# shudian.net
KiCad netlist of a schematic drawn in Altium Designer
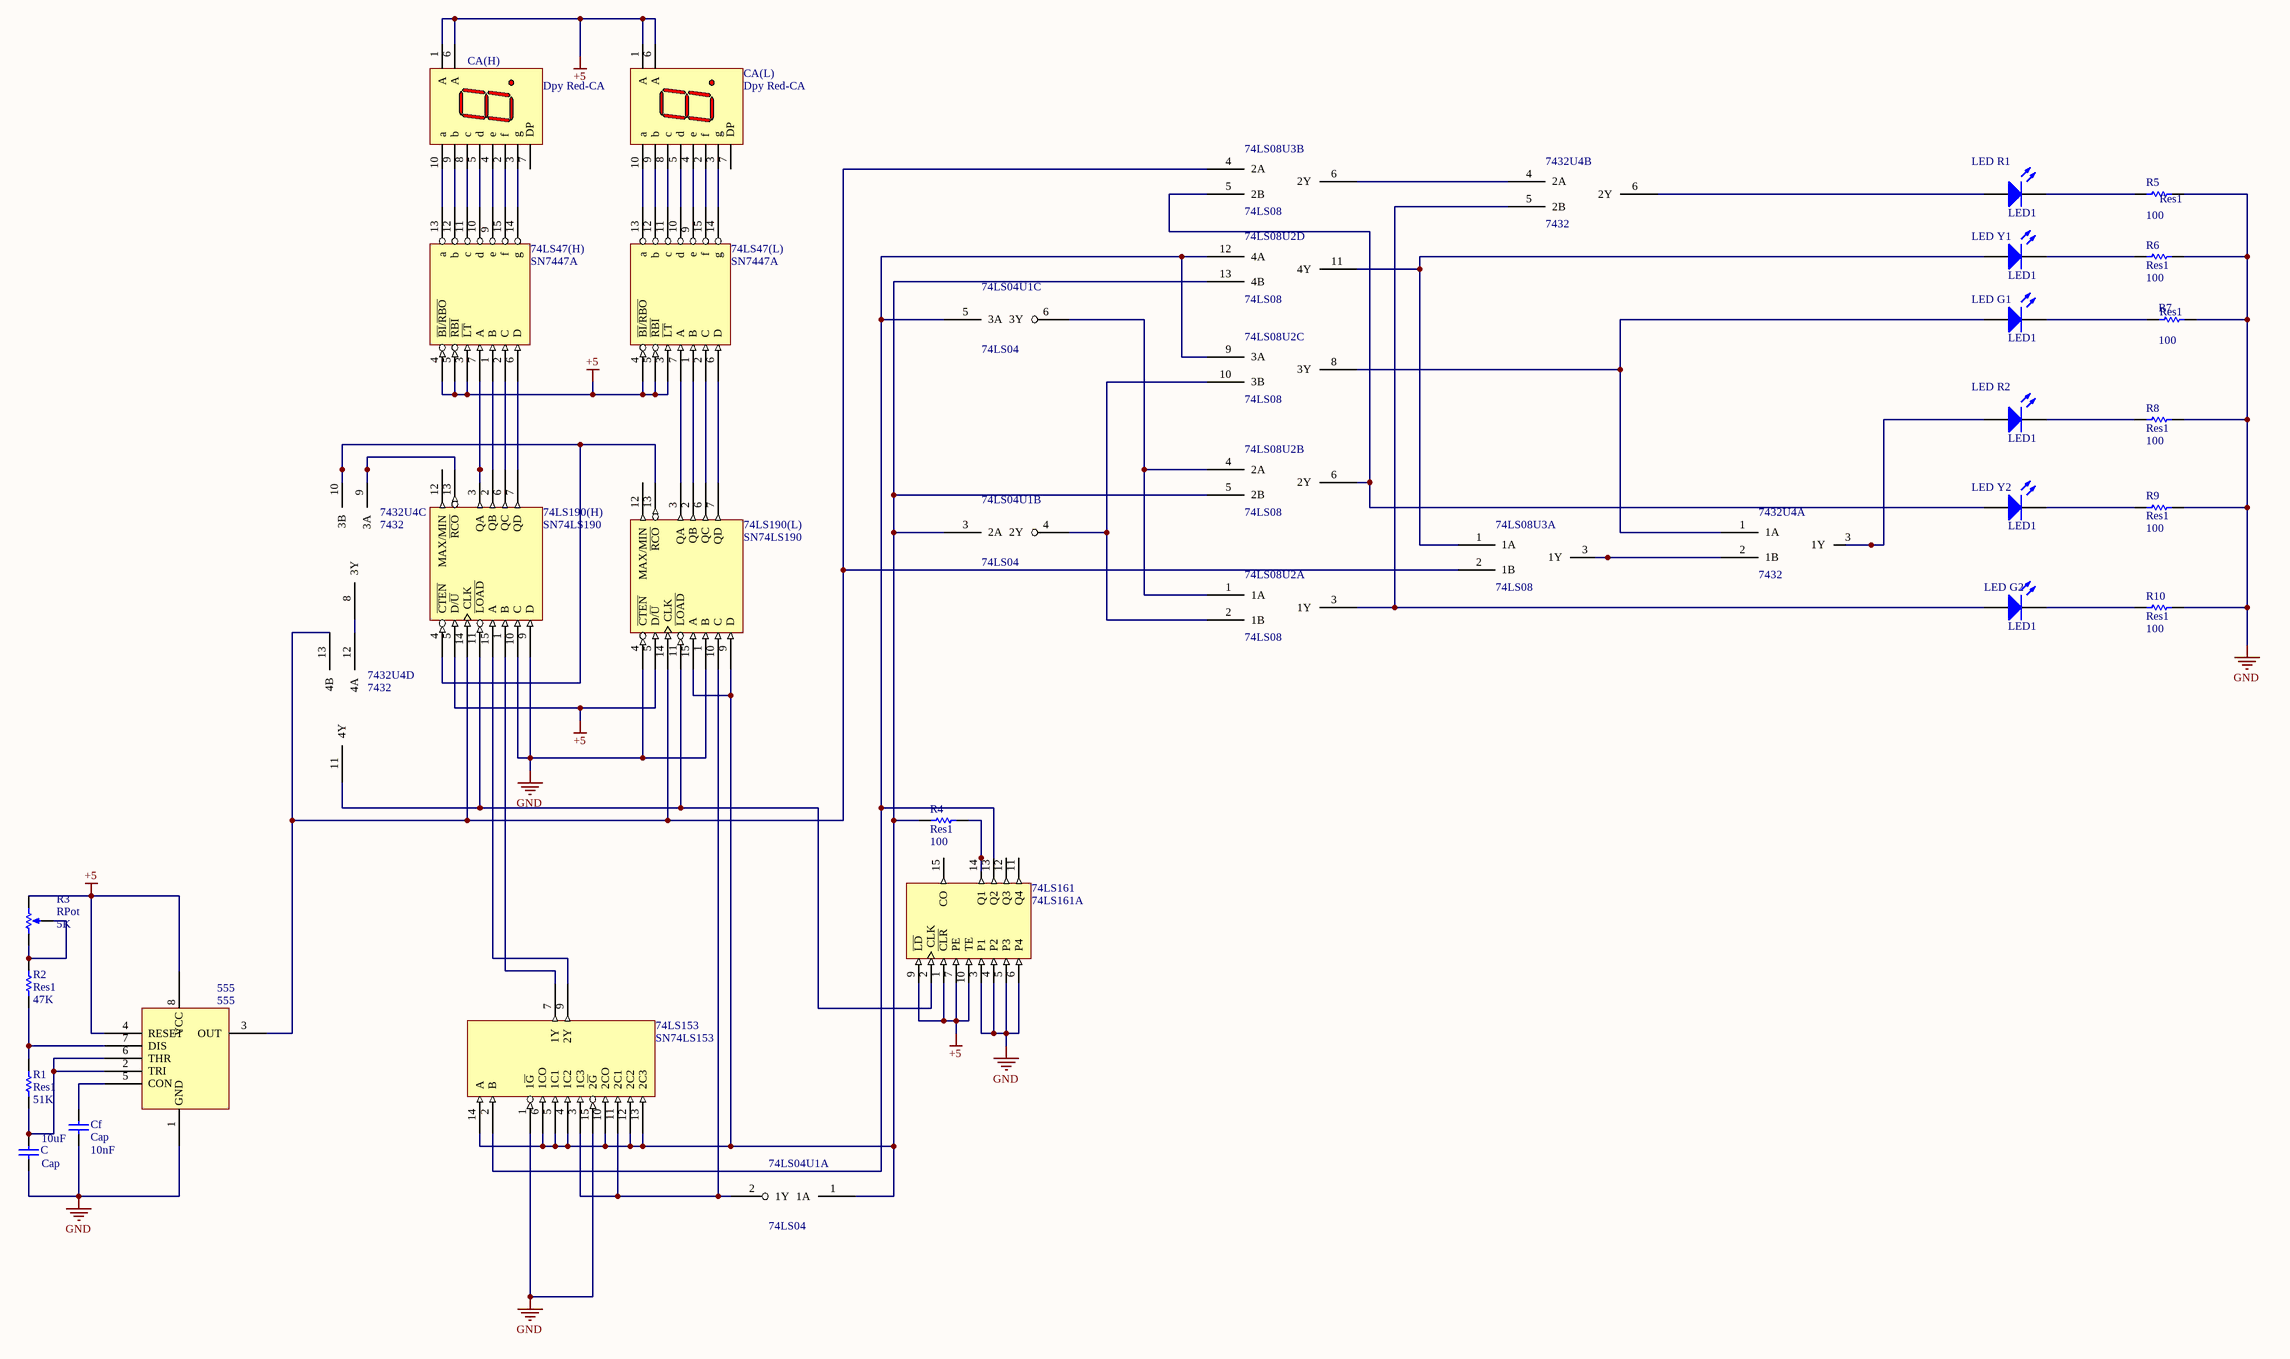
[diagram p0: shudian.schdoc]

(export (version "E")
  (design (tool "Eeschema 10.0.6"))
  (components
    (comp (ref "74LS04U1") (value "74LS04") (footprint "DIP14") (libsource (lib "shudian") (part "74LS04")))
    (comp (ref "74LS08U2") (value "74LS08") (footprint "DIP14") (libsource (lib "shudian") (part "74LS08")))
    (comp (ref "74LS08U3") (value "74LS08") (footprint "DIP14") (libsource (lib "shudian") (part "74LS08")))
    (comp (ref "74LS47(H)")
      (value "SN7447A")
      (footprint "DIP16")
      (description "BCD-To-SEVEN-SEGMENT DEC DRV")
      (libsource (lib "1.4 - 74系列TTL芯片") (part "SN7446A"))
    )
    (comp (ref "74LS47(L)")
      (value "SN7447A")
      (footprint "DIP-16")
      (description "BCD-To-SEVEN-SEGMENT DEC DRV")
      (libsource (lib "1.4 - 74系列TTL芯片") (part "SN7446A"))
    )
    (comp (ref "74LS153")
      (value "SN74LS153")
      (footprint "DIP16")
      (description "DUAL 4-1 LINE DATA SELEC/MUX")
      (libsource (lib "1.4 - 74系列TTL芯片") (part "SN74LS153"))
    )
    (comp (ref "74LS161")
      (value "74LS161A")
      (footprint "DIP-16")
      (description "Synchronous 4-Bit Binary Counter with Direct Clear")
      (libsource (lib "1.4 - 74系列TTL芯片") (part "74LS161A"))
    )
    (comp (ref "74LS190(H)")
      (value "SN74LS190")
      (footprint "DIP-16")
      (description "SYN UP/DOWN CNT DOWN/UP MODE CONTTOL")
      (libsource (lib "1.4 - 74系列TTL芯片") (part "SN74LS190"))
    )
    (comp (ref "74LS190(L)")
      (value "SN74LS190")
      (footprint "DIP-16")
      (description "SYN UP/DOWN CNT DOWN/UP MODE CONTTOL")
      (libsource (lib "1.4 - 74系列TTL芯片") (part "SN74LS190"))
    )
    (comp (ref "555") (value "555") (footprint "DIP8") (libsource (lib "Schlib1") (part "555")))
    (comp (ref "7432U4") (value "7432") (footprint "DIP14") (libsource (lib "shudian") (part "7432")))
    (comp (ref "C")
      (value "Cap")
      (footprint "RAD-0.3")
      (description "Capacitor")
      (fields (field (name "ALTIUM_VALUE") "10uF") (field (name "PUBLISHER") "Altium Limited"))
      (libsource (lib "Miscellaneous Devices") (part "Cap"))
    )
    (comp (ref "CA(H)")
      (value "Dpy Red-CA")
      (footprint "A")
      (description "7.62 mm Black Surface HER 7-Segment Display: CA, RH DP")
      (fields (field (name "PUBLISHER") "Altium Limited"))
      (libsource (lib "Miscellaneous Devices") (part "Dpy Red-CA"))
    )
    (comp (ref "CA(L)")
      (value "Dpy Red-CA")
      (footprint "A")
      (description "7.62 mm Black Surface HER 7-Segment Display: CA, RH DP")
      (fields (field (name "PUBLISHER") "Altium Limited"))
      (libsource (lib "Miscellaneous Devices") (part "Dpy Red-CA"))
    )
    (comp (ref "Cf")
      (value "Cap")
      (footprint "RAD-0.3")
      (description "Capacitor")
      (fields (field (name "ALTIUM_VALUE") "10nF") (field (name "PUBLISHER") "Altium Limited"))
      (libsource (lib "Miscellaneous Devices") (part "Cap"))
    )
    (comp (ref "LED G1")
      (value "LED1")
      (footprint "LED-1")
      (description "Typical RED GaAs LED")
      (fields (field (name "PUBLISHER") "Altium Limited"))
      (libsource (lib "Miscellaneous Devices") (part "LED1"))
    )
    (comp (ref "LED G2")
      (value "LED1")
      (footprint "LED-1")
      (description "Typical RED GaAs LED")
      (fields (field (name "PUBLISHER") "Altium Limited"))
      (libsource (lib "Miscellaneous Devices") (part "LED1"))
    )
    (comp (ref "LED R1")
      (value "LED1")
      (footprint "LED-1")
      (description "Typical RED GaAs LED")
      (fields (field (name "PUBLISHER") "Altium Limited"))
      (libsource (lib "Miscellaneous Devices") (part "LED1"))
    )
    (comp (ref "LED R2")
      (value "LED1")
      (footprint "LED-1")
      (description "Typical RED GaAs LED")
      (fields (field (name "PUBLISHER") "Altium Limited"))
      (libsource (lib "Miscellaneous Devices") (part "LED1"))
    )
    (comp (ref "LED Y1")
      (value "LED1")
      (footprint "LED-1")
      (description "Typical RED GaAs LED")
      (fields (field (name "PUBLISHER") "Altium Limited"))
      (libsource (lib "Miscellaneous Devices") (part "LED1"))
    )
    (comp (ref "LED Y2")
      (value "LED1")
      (footprint "LED-1")
      (description "Typical RED GaAs LED")
      (fields (field (name "PUBLISHER") "Altium Limited"))
      (libsource (lib "Miscellaneous Devices") (part "LED1"))
    )
    (comp (ref "R1")
      (value "Res1")
      (footprint "AXIAL-0.3")
      (description "Resistor")
      (fields (field (name "ALTIUM_VALUE") "51K") (field (name "PUBLISHER") "Altium Limited"))
      (libsource (lib "Miscellaneous Devices") (part "Res1"))
    )
    (comp (ref "R2")
      (value "Res1")
      (footprint "AXIAL-0.3")
      (description "Resistor")
      (fields (field (name "ALTIUM_VALUE") "47K") (field (name "PUBLISHER") "Altium Limited"))
      (libsource (lib "Miscellaneous Devices") (part "Res1"))
    )
    (comp (ref "R3")
      (value "RPot")
      (footprint "VR5")
      (description "Potentiometer")
      (fields (field (name "ALTIUM_VALUE") "5K") (field (name "PUBLISHER") "Altium Limited"))
      (libsource (lib "Miscellaneous Devices") (part "RPot"))
    )
    (comp (ref "R4")
      (value "Res1")
      (footprint "AXIAL-0.3")
      (description "Resistor")
      (fields (field (name "ALTIUM_VALUE") "100") (field (name "PUBLISHER") "Altium Limited"))
      (libsource (lib "Miscellaneous Devices") (part "Res1"))
    )
    (comp (ref "R5")
      (value "Res1")
      (footprint "AXIAL-0.3")
      (description "Resistor")
      (fields (field (name "ALTIUM_VALUE") "100") (field (name "PUBLISHER") "Altium Limited"))
      (libsource (lib "Miscellaneous Devices") (part "Res1"))
    )
    (comp (ref "R6")
      (value "Res1")
      (footprint "AXIAL-0.3")
      (description "Resistor")
      (fields (field (name "ALTIUM_VALUE") "100") (field (name "PUBLISHER") "Altium Limited"))
      (libsource (lib "Miscellaneous Devices") (part "Res1"))
    )
    (comp (ref "R7")
      (value "Res1")
      (footprint "AXIAL-0.3")
      (description "Resistor")
      (fields (field (name "ALTIUM_VALUE") "100") (field (name "PUBLISHER") "Altium Limited"))
      (libsource (lib "Miscellaneous Devices") (part "Res1"))
    )
    (comp (ref "R8")
      (value "Res1")
      (footprint "AXIAL-0.3")
      (description "Resistor")
      (fields (field (name "ALTIUM_VALUE") "100") (field (name "PUBLISHER") "Altium Limited"))
      (libsource (lib "Miscellaneous Devices") (part "Res1"))
    )
    (comp (ref "R9")
      (value "Res1")
      (footprint "AXIAL-0.3")
      (description "Resistor")
      (fields (field (name "ALTIUM_VALUE") "100") (field (name "PUBLISHER") "Altium Limited"))
      (libsource (lib "Miscellaneous Devices") (part "Res1"))
    )
    (comp (ref "R10")
      (value "Res1")
      (footprint "AXIAL-0.3")
      (description "Resistor")
      (fields (field (name "ALTIUM_VALUE") "100") (field (name "PUBLISHER") "Altium Limited"))
      (libsource (lib "Miscellaneous Devices") (part "Res1"))
    )
  )
  (nets
    (net (code "1") (name "+5") (class "Default")
      (node (ref "555") (pin "4") (pinfunction "RESET_4") (pintype "passive"))
      (node (ref "555") (pin "8") (pinfunction "VCC_8") (pintype "passive"))
      (node (ref "74LS161") (pin "1") (pinfunction "~{CLR}_1") (pintype "input"))
      (node (ref "74LS161") (pin "10") (pinfunction "TE_10") (pintype "input"))
      (node (ref "74LS161") (pin "7") (pinfunction "PE_7") (pintype "input"))
      (node (ref "74LS161") (pin "9") (pinfunction "~{LD}_9") (pintype "input"))
      (node (ref "74LS190(H)") (pin "5") (pinfunction "D/~{U}_5") (pintype "input"))
      (node (ref "74LS190(L)") (pin "5") (pinfunction "D/~{U}_5") (pintype "input"))
      (node (ref "74LS47(H)") (pin "3") (pinfunction "~{LT}_3") (pintype "input"))
      (node (ref "74LS47(H)") (pin "4") (pinfunction "~{BI}/~{RBO}_4") (pintype "input"))
      (node (ref "74LS47(H)") (pin "5") (pinfunction "~{RBI}_5") (pintype "input"))
      (node (ref "74LS47(L)") (pin "3") (pinfunction "~{LT}_3") (pintype "input"))
      (node (ref "74LS47(L)") (pin "4") (pinfunction "~{BI}/~{RBO}_4") (pintype "input"))
      (node (ref "74LS47(L)") (pin "5") (pinfunction "~{RBI}_5") (pintype "input"))
      (node (ref "CA(H)") (pin "1") (pinfunction "A_1") (pintype "passive"))
      (node (ref "CA(H)") (pin "6") (pinfunction "A_6") (pintype "passive"))
      (node (ref "CA(L)") (pin "1") (pinfunction "A_1") (pintype "passive"))
      (node (ref "CA(L)") (pin "6") (pinfunction "A_6") (pintype "passive"))
      (node (ref "R3") (pin "2") (pinfunction "BOT_2") (pintype "passive"))
    )
    (net (code "2") (name "GND") (class "Default")
      (node (ref "555") (pin "1") (pinfunction "GND_1") (pintype "passive"))
      (node (ref "74LS153") (pin "1") (pinfunction "1~{G}_1") (pintype "input"))
      (node (ref "74LS153") (pin "15") (pinfunction "2~{G}_15") (pintype "input"))
      (node (ref "74LS153") (pin "8") (pinfunction "GND_8") (pintype "power_in"))
      (node (ref "74LS161") (pin "3") (pinfunction "P1_3") (pintype "input"))
      (node (ref "74LS161") (pin "4") (pinfunction "P2_4") (pintype "input"))
      (node (ref "74LS161") (pin "5") (pinfunction "P3_5") (pintype "input"))
      (node (ref "74LS161") (pin "6") (pinfunction "P4_6") (pintype "input"))
      (node (ref "74LS161") (pin "8") (pinfunction "GND_8") (pintype "power_in"))
      (node (ref "74LS190(H)") (pin "10") (pinfunction "C_10") (pintype "input"))
      (node (ref "74LS190(H)") (pin "8") (pinfunction "GND_8") (pintype "power_in"))
      (node (ref "74LS190(H)") (pin "9") (pinfunction "D_9") (pintype "input"))
      (node (ref "74LS190(L)") (pin "1") (pinfunction "B_1") (pintype "input"))
      (node (ref "74LS190(L)") (pin "4") (pinfunction "~{CTEN}_4") (pintype "input"))
      (node (ref "74LS190(L)") (pin "8") (pinfunction "GND_8") (pintype "power_in"))
      (node (ref "74LS47(H)") (pin "8") (pinfunction "GND_8") (pintype "power_in"))
      (node (ref "74LS47(L)") (pin "8") (pinfunction "GND_8") (pintype "power_in"))
      (node (ref "C") (pin "1") (pinfunction "1_1") (pintype "passive"))
      (node (ref "Cf") (pin "1") (pinfunction "1_1") (pintype "passive"))
      (node (ref "R10") (pin "2") (pinfunction "2_2") (pintype "passive"))
      (node (ref "R5") (pin "2") (pinfunction "2_2") (pintype "passive"))
      (node (ref "R6") (pin "2") (pinfunction "2_2") (pintype "passive"))
      (node (ref "R7") (pin "2") (pinfunction "2_2") (pintype "passive"))
      (node (ref "R8") (pin "2") (pinfunction "2_2") (pintype "passive"))
      (node (ref "R9") (pin "2") (pinfunction "2_2") (pintype "passive"))
    )
    (net (code "3") (name "Net-(74LS04U1A-1A)") (class "Default")
      (node (ref "74LS04U1") (pin "1") (pinfunction "1A_1") (pintype "passive"))
      (node (ref "74LS04U1") (pin "3") (pinfunction "2A_3") (pintype "passive"))
      (node (ref "74LS08U2") (pin "13") (pinfunction "4B_13") (pintype "passive"))
      (node (ref "74LS08U2") (pin "5") (pinfunction "2B_5") (pintype "passive"))
      (node (ref "74LS153") (pin "10") (pinfunction "2CO_10") (pintype "input"))
      (node (ref "74LS153") (pin "12") (pinfunction "2C2_12") (pintype "input"))
      (node (ref "74LS153") (pin "13") (pinfunction "2C3_13") (pintype "input"))
      (node (ref "74LS153") (pin "14") (pinfunction "A_14") (pintype "input"))
      (node (ref "74LS153") (pin "4") (pinfunction "1C2_4") (pintype "input"))
      (node (ref "74LS153") (pin "5") (pinfunction "1C1_5") (pintype "input"))
      (node (ref "74LS153") (pin "6") (pinfunction "1CO_6") (pintype "input"))
      (node (ref "74LS190(L)") (pin "15") (pinfunction "A_15") (pintype "input"))
      (node (ref "74LS190(L)") (pin "9") (pinfunction "D_9") (pintype "input"))
      (node (ref "R4") (pin "1") (pinfunction "1_1") (pintype "passive"))
    )
    (net (code "4") (name "Net-(74LS04U1A-1Y)") (class "Default")
      (node (ref "74LS04U1") (pin "2") (pinfunction "1Y_2") (pintype "passive"))
      (node (ref "74LS153") (pin "11") (pinfunction "2C1_11") (pintype "input"))
      (node (ref "74LS153") (pin "3") (pinfunction "1C3_3") (pintype "input"))
      (node (ref "74LS190(L)") (pin "10") (pinfunction "C_10") (pintype "input"))
    )
    (net (code "5") (name "Net-(74LS04U1B-2Y)") (class "Default")
      (node (ref "74LS04U1") (pin "4") (pinfunction "2Y_4") (pintype "passive"))
      (node (ref "74LS08U2") (pin "10") (pinfunction "3B_10") (pintype "passive"))
      (node (ref "74LS08U2") (pin "2") (pinfunction "1B_2") (pintype "passive"))
    )
    (net (code "6") (name "Net-(74LS04U1C-3A)") (class "Default")
      (node (ref "74LS04U1") (pin "5") (pinfunction "3A_5") (pintype "passive"))
      (node (ref "74LS08U2") (pin "12") (pinfunction "4A_12") (pintype "passive"))
      (node (ref "74LS08U2") (pin "9") (pinfunction "3A_9") (pintype "passive"))
      (node (ref "74LS153") (pin "2") (pinfunction "B_2") (pintype "input"))
      (node (ref "74LS161") (pin "13") (pinfunction "Q2_13") (pintype "output"))
    )
    (net (code "7") (name "Net-(74LS04U1C-3Y)") (class "Default")
      (node (ref "74LS04U1") (pin "6") (pinfunction "3Y_6") (pintype "passive"))
      (node (ref "74LS08U2") (pin "1") (pinfunction "1A_1") (pintype "passive"))
      (node (ref "74LS08U2") (pin "4") (pinfunction "2A_4") (pintype "passive"))
    )
    (net (code "8") (name "Net-(74LS08U2B-2Y)") (class "Default")
      (node (ref "74LS08U2") (pin "6") (pinfunction "2Y_6") (pintype "passive"))
      (node (ref "74LS08U3") (pin "5") (pinfunction "2B_5") (pintype "passive"))
      (node (ref "LED Y2") (pin "1") (pinfunction "A_1") (pintype "passive"))
    )
    (net (code "9") (name "Net-(74LS08U2D-4Y)") (class "Default")
      (node (ref "74LS08U2") (pin "11") (pinfunction "4Y_11") (pintype "passive"))
      (node (ref "74LS08U3") (pin "1") (pinfunction "1A_1") (pintype "passive"))
      (node (ref "LED Y1") (pin "1") (pinfunction "A_1") (pintype "passive"))
    )
    (net (code "10") (name "Net-(74LS47(H)-a)") (class "Default")
      (node (ref "74LS47(H)") (pin "13") (pinfunction "a_13") (pintype "open_collector"))
      (node (ref "CA(H)") (pin "10") (pinfunction "a_10") (pintype "passive"))
    )
    (net (code "11") (name "Net-(74LS47(H)-b)") (class "Default")
      (node (ref "74LS47(H)") (pin "12") (pinfunction "b_12") (pintype "open_collector"))
      (node (ref "CA(H)") (pin "9") (pinfunction "b_9") (pintype "passive"))
    )
    (net (code "12") (name "Net-(74LS47(H)-c)") (class "Default")
      (node (ref "74LS47(H)") (pin "11") (pinfunction "c_11") (pintype "open_collector"))
      (node (ref "CA(H)") (pin "8") (pinfunction "c_8") (pintype "passive"))
    )
    (net (code "13") (name "Net-(74LS47(H)-d)") (class "Default")
      (node (ref "74LS47(H)") (pin "10") (pinfunction "d_10") (pintype "open_collector"))
      (node (ref "CA(H)") (pin "5") (pinfunction "d_5") (pintype "passive"))
    )
    (net (code "14") (name "Net-(74LS47(H)-e)") (class "Default")
      (node (ref "74LS47(H)") (pin "9") (pinfunction "e_9") (pintype "open_collector"))
      (node (ref "CA(H)") (pin "4") (pinfunction "e_4") (pintype "passive"))
    )
    (net (code "15") (name "Net-(74LS47(H)-f)") (class "Default")
      (node (ref "74LS47(H)") (pin "15") (pinfunction "f_15") (pintype "open_collector"))
      (node (ref "CA(H)") (pin "2") (pinfunction "f_2") (pintype "passive"))
    )
    (net (code "16") (name "Net-(74LS47(H)-g)") (class "Default")
      (node (ref "74LS47(H)") (pin "14") (pinfunction "g_14") (pintype "open_collector"))
      (node (ref "CA(H)") (pin "3") (pinfunction "g_3") (pintype "passive"))
    )
    (net (code "17") (name "Net-(74LS47(L)-a)") (class "Default")
      (node (ref "74LS47(L)") (pin "13") (pinfunction "a_13") (pintype "open_collector"))
      (node (ref "CA(L)") (pin "10") (pinfunction "a_10") (pintype "passive"))
    )
    (net (code "18") (name "Net-(74LS47(L)-b)") (class "Default")
      (node (ref "74LS47(L)") (pin "12") (pinfunction "b_12") (pintype "open_collector"))
      (node (ref "CA(L)") (pin "9") (pinfunction "b_9") (pintype "passive"))
    )
    (net (code "19") (name "Net-(74LS47(L)-c)") (class "Default")
      (node (ref "74LS47(L)") (pin "11") (pinfunction "c_11") (pintype "open_collector"))
      (node (ref "CA(L)") (pin "8") (pinfunction "c_8") (pintype "passive"))
    )
    (net (code "20") (name "Net-(74LS47(L)-d)") (class "Default")
      (node (ref "74LS47(L)") (pin "10") (pinfunction "d_10") (pintype "open_collector"))
      (node (ref "CA(L)") (pin "5") (pinfunction "d_5") (pintype "passive"))
    )
    (net (code "21") (name "Net-(74LS47(L)-e)") (class "Default")
      (node (ref "74LS47(L)") (pin "9") (pinfunction "e_9") (pintype "open_collector"))
      (node (ref "CA(L)") (pin "4") (pinfunction "e_4") (pintype "passive"))
    )
    (net (code "22") (name "Net-(74LS47(L)-f)") (class "Default")
      (node (ref "74LS47(L)") (pin "15") (pinfunction "f_15") (pintype "open_collector"))
      (node (ref "CA(L)") (pin "2") (pinfunction "f_2") (pintype "passive"))
    )
    (net (code "23") (name "Net-(74LS47(L)-g)") (class "Default")
      (node (ref "74LS47(L)") (pin "14") (pinfunction "g_14") (pintype "open_collector"))
      (node (ref "CA(L)") (pin "3") (pinfunction "g_3") (pintype "passive"))
    )
    (net (code "24") (name "Net-(74LS153-1Y)") (class "Default")
      (node (ref "74LS153") (pin "7") (pinfunction "1Y_7") (pintype "output"))
      (node (ref "74LS190(H)") (pin "1") (pinfunction "B_1") (pintype "input"))
    )
    (net (code "25") (name "Net-(74LS153-2Y)") (class "Default")
      (node (ref "74LS153") (pin "9") (pinfunction "2Y_9") (pintype "output"))
      (node (ref "74LS190(H)") (pin "15") (pinfunction "A_15") (pintype "input"))
    )
    (net (code "26") (name "Net-(74LS161-Q1)") (class "Default")
      (node (ref "74LS161") (pin "14") (pinfunction "Q1_14") (pintype "output"))
      (node (ref "R4") (pin "2") (pinfunction "2_2") (pintype "passive"))
    )
    (net (code "27") (name "Net-(74LS190(H)-QA)") (class "Default")
      (node (ref "74LS190(H)") (pin "3") (pinfunction "QA_3") (pintype "output"))
      (node (ref "74LS47(H)") (pin "7") (pinfunction "A_7") (pintype "input"))
    )
    (net (code "28") (name "Net-(74LS190(H)-QB)") (class "Default")
      (node (ref "74LS190(H)") (pin "2") (pinfunction "QB_2") (pintype "output"))
      (node (ref "74LS47(H)") (pin "1") (pinfunction "B_1") (pintype "input"))
    )
    (net (code "29") (name "Net-(74LS190(H)-QC)") (class "Default")
      (node (ref "74LS190(H)") (pin "6") (pinfunction "QC_6") (pintype "output"))
      (node (ref "74LS47(H)") (pin "2") (pinfunction "C_2") (pintype "input"))
    )
    (net (code "30") (name "Net-(74LS190(H)-QD)") (class "Default")
      (node (ref "74LS190(H)") (pin "7") (pinfunction "QD_7") (pintype "output"))
      (node (ref "74LS47(H)") (pin "6") (pinfunction "D_6") (pintype "input"))
    )
    (net (code "31") (name "Net-(74LS190(L)-QA)") (class "Default")
      (node (ref "74LS190(L)") (pin "3") (pinfunction "QA_3") (pintype "output"))
      (node (ref "74LS47(L)") (pin "7") (pinfunction "A_7") (pintype "input"))
    )
    (net (code "32") (name "Net-(74LS190(L)-QB)") (class "Default")
      (node (ref "74LS190(L)") (pin "2") (pinfunction "QB_2") (pintype "output"))
      (node (ref "74LS47(L)") (pin "1") (pinfunction "B_1") (pintype "input"))
    )
    (net (code "33") (name "Net-(74LS190(L)-QC)") (class "Default")
      (node (ref "74LS190(L)") (pin "6") (pinfunction "QC_6") (pintype "output"))
      (node (ref "74LS47(L)") (pin "2") (pinfunction "C_2") (pintype "input"))
    )
    (net (code "34") (name "Net-(74LS190(L)-QD)") (class "Default")
      (node (ref "74LS190(L)") (pin "7") (pinfunction "QD_7") (pintype "output"))
      (node (ref "74LS47(L)") (pin "6") (pinfunction "D_6") (pintype "input"))
    )
    (net (code "35") (name "Net-(555-CON)") (class "Default")
      (node (ref "555") (pin "5") (pinfunction "CON_5") (pintype "passive"))
      (node (ref "Cf") (pin "2") (pinfunction "2_2") (pintype "passive"))
    )
    (net (code "36") (name "Net-(555-DIS)") (class "Default")
      (node (ref "555") (pin "7") (pinfunction "DIS_7") (pintype "passive"))
      (node (ref "R1") (pin "2") (pinfunction "2_2") (pintype "passive"))
      (node (ref "R2") (pin "1") (pinfunction "1_1") (pintype "passive"))
    )
    (net (code "37") (name "Net-(555-OUT)") (class "Default")
      (node (ref "555") (pin "3") (pinfunction "OUT_3") (pintype "passive"))
      (node (ref "7432U4") (pin "13") (pinfunction "4B_13") (pintype "passive"))
      (node (ref "74LS08U3") (pin "2") (pinfunction "1B_2") (pintype "passive"))
      (node (ref "74LS08U3") (pin "4") (pinfunction "2A_4") (pintype "passive"))
      (node (ref "74LS190(H)") (pin "14") (pinfunction "CLK_14") (pintype "input"))
      (node (ref "74LS190(L)") (pin "14") (pinfunction "CLK_14") (pintype "input"))
    )
    (net (code "38") (name "Net-(555-THR)") (class "Default")
      (node (ref "555") (pin "2") (pinfunction "TRI_2") (pintype "passive"))
      (node (ref "555") (pin "6") (pinfunction "THR_6") (pintype "passive"))
      (node (ref "C") (pin "2") (pinfunction "2_2") (pintype "passive"))
      (node (ref "R1") (pin "1") (pinfunction "1_1") (pintype "passive"))
    )
    (net (code "39") (name "Net-(7432U4A-1A)") (class "Default")
      (node (ref "7432U4") (pin "1") (pinfunction "1A_1") (pintype "passive"))
      (node (ref "74LS08U2") (pin "8") (pinfunction "3Y_8") (pintype "passive"))
      (node (ref "LED G1") (pin "1") (pinfunction "A_1") (pintype "passive"))
    )
    (net (code "40") (name "Net-(7432U4A-1B)") (class "Default")
      (node (ref "7432U4") (pin "2") (pinfunction "1B_2") (pintype "passive"))
      (node (ref "74LS08U3") (pin "3") (pinfunction "1Y_3") (pintype "passive"))
    )
    (net (code "41") (name "Net-(7432U4A-1Y)") (class "Default")
      (node (ref "7432U4") (pin "3") (pinfunction "1Y_3") (pintype "passive"))
      (node (ref "LED R2") (pin "1") (pinfunction "A_1") (pintype "passive"))
    )
    (net (code "42") (name "Net-(7432U4B-2A)") (class "Default")
      (node (ref "7432U4") (pin "4") (pinfunction "2A_4") (pintype "passive"))
      (node (ref "74LS08U3") (pin "6") (pinfunction "2Y_6") (pintype "passive"))
    )
    (net (code "43") (name "Net-(7432U4B-2B)") (class "Default")
      (node (ref "7432U4") (pin "5") (pinfunction "2B_5") (pintype "passive"))
      (node (ref "74LS08U2") (pin "3") (pinfunction "1Y_3") (pintype "passive"))
      (node (ref "LED G2") (pin "1") (pinfunction "A_1") (pintype "passive"))
    )
    (net (code "44") (name "Net-(7432U4B-2Y)") (class "Default")
      (node (ref "7432U4") (pin "6") (pinfunction "2Y_6") (pintype "passive"))
      (node (ref "LED R1") (pin "1") (pinfunction "A_1") (pintype "passive"))
    )
    (net (code "45") (name "Net-(7432U4C-3A)") (class "Default")
      (node (ref "7432U4") (pin "9") (pinfunction "3A_9") (pintype "passive"))
      (node (ref "74LS190(H)") (pin "13") (pinfunction "~{RCO}_13") (pintype "output"))
    )
    (net (code "46") (name "Net-(7432U4C-3B)") (class "Default")
      (node (ref "7432U4") (pin "10") (pinfunction "3B_10") (pintype "passive"))
      (node (ref "74LS190(H)") (pin "4") (pinfunction "~{CTEN}_4") (pintype "input"))
      (node (ref "74LS190(L)") (pin "13") (pinfunction "~{RCO}_13") (pintype "output"))
    )
    (net (code "47") (name "Net-(7432U4C-3Y)") (class "Default")
      (node (ref "7432U4") (pin "12") (pinfunction "4A_12") (pintype "passive"))
      (node (ref "7432U4") (pin "8") (pinfunction "3Y_8") (pintype "passive"))
    )
    (net (code "48") (name "Net-(7432U4D-4Y)") (class "Default")
      (node (ref "7432U4") (pin "11") (pinfunction "4Y_11") (pintype "passive"))
      (node (ref "74LS161") (pin "2") (pinfunction "CLK_2") (pintype "input"))
      (node (ref "74LS190(H)") (pin "11") (pinfunction "~{LOAD}_11") (pintype "input"))
      (node (ref "74LS190(L)") (pin "11") (pinfunction "~{LOAD}_11") (pintype "input"))
    )
    (net (code "49") (name "Net-(LED G1-K)") (class "Default")
      (node (ref "LED G1") (pin "2") (pinfunction "K_2") (pintype "passive"))
      (node (ref "R7") (pin "1") (pinfunction "1_1") (pintype "passive"))
    )
    (net (code "50") (name "Net-(LED G2-K)") (class "Default")
      (node (ref "LED G2") (pin "2") (pinfunction "K_2") (pintype "passive"))
      (node (ref "R10") (pin "1") (pinfunction "1_1") (pintype "passive"))
    )
    (net (code "51") (name "Net-(LED R1-K)") (class "Default")
      (node (ref "LED R1") (pin "2") (pinfunction "K_2") (pintype "passive"))
      (node (ref "R5") (pin "1") (pinfunction "1_1") (pintype "passive"))
    )
    (net (code "52") (name "Net-(LED R2-K)") (class "Default")
      (node (ref "LED R2") (pin "2") (pinfunction "K_2") (pintype "passive"))
      (node (ref "R8") (pin "1") (pinfunction "1_1") (pintype "passive"))
    )
    (net (code "53") (name "Net-(LED Y1-K)") (class "Default")
      (node (ref "LED Y1") (pin "2") (pinfunction "K_2") (pintype "passive"))
      (node (ref "R6") (pin "1") (pinfunction "1_1") (pintype "passive"))
    )
    (net (code "54") (name "Net-(LED Y2-K)") (class "Default")
      (node (ref "LED Y2") (pin "2") (pinfunction "K_2") (pintype "passive"))
      (node (ref "R9") (pin "1") (pinfunction "1_1") (pintype "passive"))
    )
    (net (code "55") (name "Net-(R3-TAP)") (class "Default")
      (node (ref "R2") (pin "2") (pinfunction "2_2") (pintype "passive"))
      (node (ref "R3") (pin "1") (pinfunction "TOP_1") (pintype "passive"))
      (node (ref "R3") (pin "3") (pinfunction "TAP_3") (pintype "passive"))
    )
    (net (code "56") (name "VCC") (class "Default")
      (node (ref "74LS153") (pin "16") (pinfunction "VCC_16") (pintype "power_in"))
      (node (ref "74LS161") (pin "16") (pinfunction "VCC_16") (pintype "power_in"))
      (node (ref "74LS190(H)") (pin "16") (pinfunction "VCC_16") (pintype "power_in"))
      (node (ref "74LS190(L)") (pin "16") (pinfunction "VCC_16") (pintype "power_in"))
      (node (ref "74LS47(H)") (pin "16") (pinfunction "VCC_16") (pintype "power_in"))
      (node (ref "74LS47(L)") (pin "16") (pinfunction "VCC_16") (pintype "power_in"))
    )
    (net (code "57") (name "unconnected-(74LS161-CO-Pad15)") (class "Default")
      (node (ref "74LS161") (pin "15") (pinfunction "CO_15") (pintype "output"))
    )
    (net (code "58") (name "unconnected-(74LS161-Q3-Pad12)") (class "Default")
      (node (ref "74LS161") (pin "12") (pinfunction "Q3_12") (pintype "output"))
    )
    (net (code "59") (name "unconnected-(74LS161-Q4-Pad11)") (class "Default")
      (node (ref "74LS161") (pin "11") (pinfunction "Q4_11") (pintype "output"))
    )
    (net (code "60") (name "unconnected-(74LS190(H)-MAX{slash}MIN-Pad12)") (class "Default")
      (node (ref "74LS190(H)") (pin "12") (pinfunction "MAX/MIN_12") (pintype "output"))
    )
    (net (code "61") (name "unconnected-(74LS190(L)-MAX{slash}MIN-Pad12)") (class "Default")
      (node (ref "74LS190(L)") (pin "12") (pinfunction "MAX/MIN_12") (pintype "output"))
    )
    (net (code "62") (name "unconnected-(CA(H)-DP-Pad7)") (class "Default")
      (node (ref "CA(H)") (pin "7") (pinfunction "DP_7") (pintype "passive"))
    )
    (net (code "63") (name "unconnected-(CA(L)-DP-Pad7)") (class "Default")
      (node (ref "CA(L)") (pin "7") (pinfunction "DP_7") (pintype "passive"))
    )
  )
)
